# design.net
KiCad netlist of a schematic drawn in Altium Designer
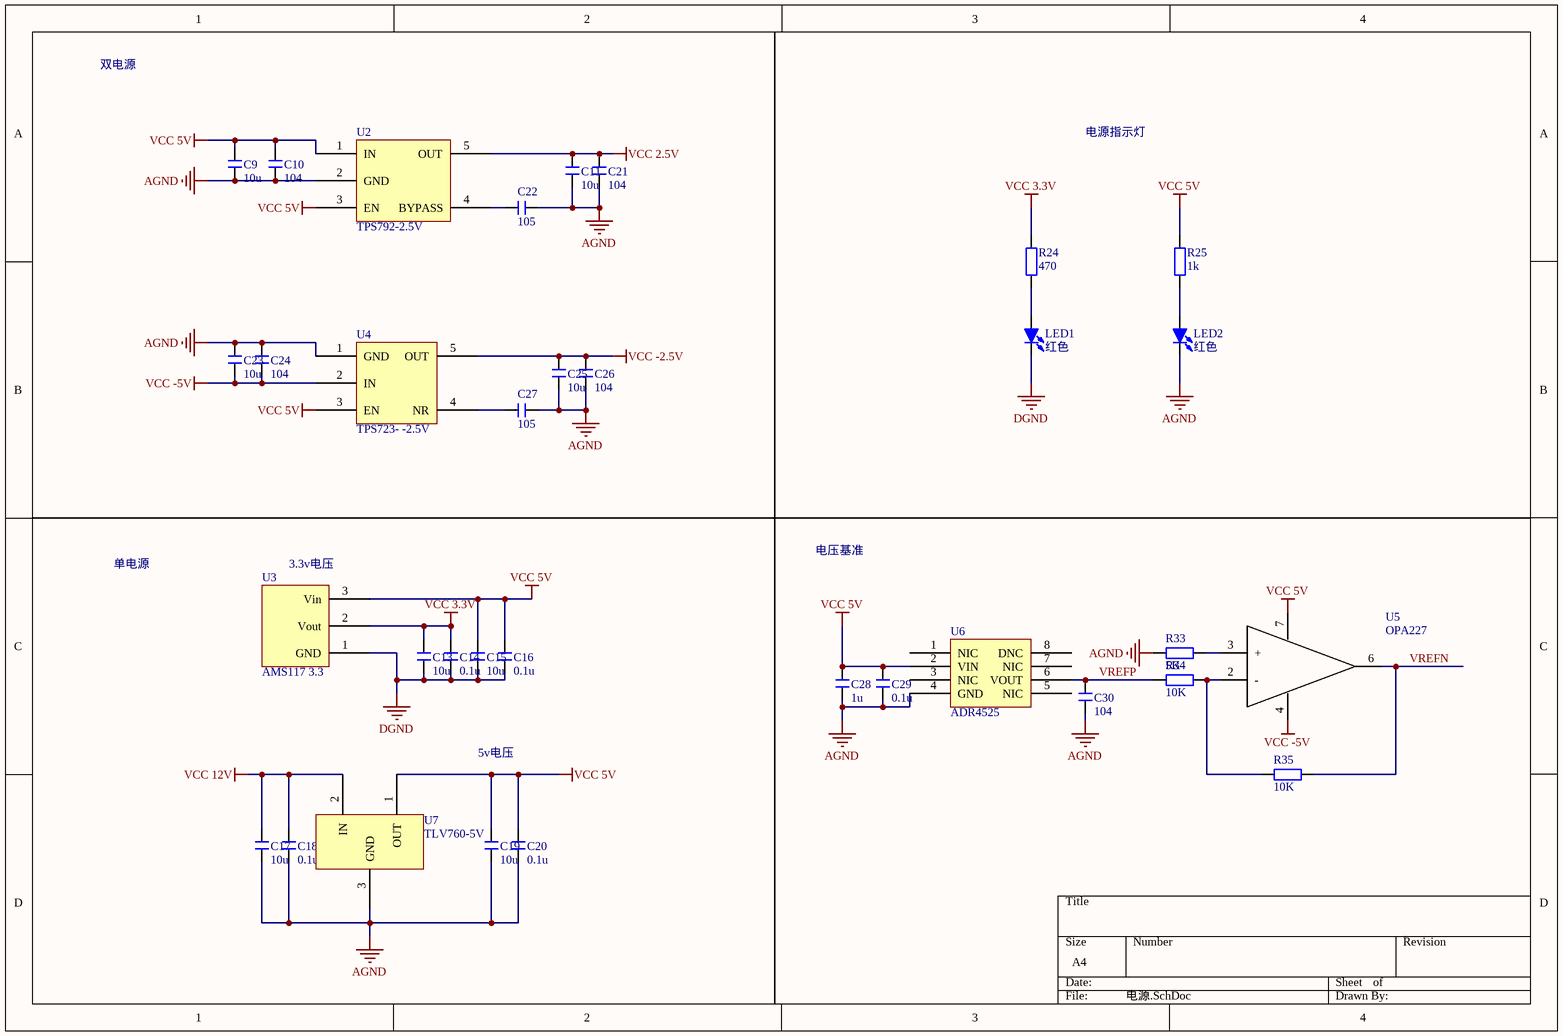
[diagram p0: 电源.SchDoc]

(export (version "E")
  (design (tool "Eeschema 10.0.6"))
  (components
    (comp (ref "C9")
      (value "10u")
      (footprint "C 0805_L")
      (description "无极性贴片电容")
      (fields (field (name "版权归属") "源创客"))
      (libsource (lib "3.1   - 电阻-电容-电感") (part "C"))
    )
    (comp (ref "C10")
      (value "104")
      (footprint "C 0805_L")
      (description "无极性贴片电容")
      (fields (field (name "版权归属") "源创客"))
      (libsource (lib "3.1   - 电阻-电容-电感") (part "C"))
    )
    (comp (ref "C11")
      (value "10u")
      (footprint "C 0805_L")
      (description "无极性贴片电容")
      (fields (field (name "版权归属") "源创客"))
      (libsource (lib "3.1   - 电阻-电容-电感") (part "C"))
    )
    (comp (ref "C13")
      (value "10u")
      (footprint "C 0805_L")
      (description "无极性贴片电容")
      (fields (field (name "版权归属") "源创客"))
      (libsource (lib "3.1   - 电阻-电容-电感") (part "C"))
    )
    (comp (ref "C14")
      (value "0.1u")
      (footprint "C 0805_L")
      (description "无极性贴片电容")
      (fields (field (name "版权归属") "源创客"))
      (libsource (lib "3.1   - 电阻-电容-电感") (part "C"))
    )
    (comp (ref "C15")
      (value "10u")
      (footprint "C 0805_L")
      (description "无极性贴片电容")
      (fields (field (name "版权归属") "源创客"))
      (libsource (lib "3.1   - 电阻-电容-电感") (part "C"))
    )
    (comp (ref "C16")
      (value "0.1u")
      (footprint "C 0805_L")
      (description "无极性贴片电容")
      (fields (field (name "版权归属") "源创客"))
      (libsource (lib "3.1   - 电阻-电容-电感") (part "C"))
    )
    (comp (ref "C17")
      (value "10u")
      (footprint "C 0805_L")
      (description "无极性贴片电容")
      (fields (field (name "版权归属") "源创客"))
      (libsource (lib "3.1   - 电阻-电容-电感") (part "C"))
    )
    (comp (ref "C18")
      (value "0.1u")
      (footprint "C 0805_L")
      (description "无极性贴片电容")
      (fields (field (name "版权归属") "源创客"))
      (libsource (lib "3.1   - 电阻-电容-电感") (part "C"))
    )
    (comp (ref "C19")
      (value "10u")
      (footprint "C 0805_L")
      (description "无极性贴片电容")
      (fields (field (name "版权归属") "源创客"))
      (libsource (lib "3.1   - 电阻-电容-电感") (part "C"))
    )
    (comp (ref "C20")
      (value "0.1u")
      (footprint "C 0805_L")
      (description "无极性贴片电容")
      (fields (field (name "版权归属") "源创客"))
      (libsource (lib "3.1   - 电阻-电容-电感") (part "C"))
    )
    (comp (ref "C21")
      (value "104")
      (footprint "C 0805_L")
      (description "无极性贴片电容")
      (fields (field (name "版权归属") "源创客"))
      (libsource (lib "3.1   - 电阻-电容-电感") (part "C"))
    )
    (comp (ref "C22")
      (value "105")
      (footprint "C 0805_L")
      (description "无极性贴片电容")
      (fields (field (name "版权归属") "源创客"))
      (libsource (lib "3.1   - 电阻-电容-电感") (part "C"))
    )
    (comp (ref "C23")
      (value "10u")
      (footprint "C 0805_L")
      (description "无极性贴片电容")
      (fields (field (name "版权归属") "源创客"))
      (libsource (lib "3.1   - 电阻-电容-电感") (part "C"))
    )
    (comp (ref "C24")
      (value "104")
      (footprint "C 0805_L")
      (description "无极性贴片电容")
      (fields (field (name "版权归属") "源创客"))
      (libsource (lib "3.1   - 电阻-电容-电感") (part "C"))
    )
    (comp (ref "C25")
      (value "10u")
      (footprint "C 0805_L")
      (description "无极性贴片电容")
      (fields (field (name "版权归属") "源创客"))
      (libsource (lib "3.1   - 电阻-电容-电感") (part "C"))
    )
    (comp (ref "C26")
      (value "104")
      (footprint "C 0805_L")
      (description "无极性贴片电容")
      (fields (field (name "版权归属") "源创客"))
      (libsource (lib "3.1   - 电阻-电容-电感") (part "C"))
    )
    (comp (ref "C27")
      (value "105")
      (footprint "C 0805_L")
      (description "无极性贴片电容")
      (fields (field (name "版权归属") "源创客"))
      (libsource (lib "3.1   - 电阻-电容-电感") (part "C"))
    )
    (comp (ref "C28")
      (value "1u")
      (footprint "C 0805_L")
      (description "无极性贴片电容")
      (fields (field (name "版权归属") "源创客"))
      (libsource (lib "3.1   - 电阻-电容-电感") (part "C"))
    )
    (comp (ref "C29")
      (value "0.1u")
      (footprint "C 0805_L")
      (description "无极性贴片电容")
      (fields (field (name "版权归属") "源创客"))
      (libsource (lib "3.1   - 电阻-电容-电感") (part "C"))
    )
    (comp (ref "C30")
      (value "104")
      (footprint "C 0805_L")
      (description "无极性贴片电容")
      (fields (field (name "版权归属") "源创客"))
      (libsource (lib "3.1   - 电阻-电容-电感") (part "C"))
    )
    (comp (ref "LED1")
      (value "红色")
      (footprint "LED 0805G")
      (description "贴片LED")
      (fields (field (name "版权归属") "源创客"))
      (libsource (lib "9.1   - LED") (part "LED-SMD"))
    )
    (comp (ref "LED2")
      (value "红色")
      (footprint "LED 0805G")
      (description "贴片LED")
      (fields (field (name "版权归属") "源创客"))
      (libsource (lib "9.1   - LED") (part "LED-SMD"))
    )
    (comp (ref "R24")
      (value "470")
      (footprint "R 0805_L")
      (description "贴片电阻")
      (fields (field (name "版权归属") "源创客"))
      (libsource (lib "3.1   - 电阻-电容-电感") (part "R"))
    )
    (comp (ref "R25")
      (value "1k")
      (footprint "R 0805_L")
      (description "贴片电阻")
      (fields (field (name "版权归属") "源创客"))
      (libsource (lib "3.1   - 电阻-电容-电感") (part "R"))
    )
    (comp (ref "R33")
      (value "5K")
      (footprint "R 0805_L")
      (description "贴片电阻")
      (fields (field (name "版权归属") "源创客"))
      (libsource (lib "3.1   - 电阻-电容-电感") (part "R"))
    )
    (comp (ref "R34")
      (value "10K")
      (footprint "R 0805_L")
      (description "贴片电阻")
      (fields (field (name "版权归属") "源创客"))
      (libsource (lib "3.1   - 电阻-电容-电感") (part "R"))
    )
    (comp (ref "R35")
      (value "10K")
      (footprint "R 0805_L")
      (description "贴片电阻")
      (fields (field (name "版权归属") "源创客"))
      (libsource (lib "3.1   - 电阻-电容-电感") (part "R"))
    )
    (comp (ref "U2")
      (value "TPS792-2.5V")
      (footprint "SOT23-5N")
      (libsource (lib "TPS792") (part "TPS792-2.5V"))
    )
    (comp (ref "U3") (value "AMS117 3.3") (footprint "SOT223_N") (libsource (lib "AMS1117") (part "AMS117")))
    (comp (ref "U4")
      (value "TPS723- -2.5V")
      (footprint "SOT23-5N")
      (libsource (lib "TPS723") (part "TPS723-  -2.5V"))
    )
    (comp (ref "U5") (value "OPA227") (footprint "SOP8_N") (libsource (lib "运放") (part "OP27")))
    (comp (ref "U6") (value "ADR4525") (footprint "SOP8_N") (libsource (lib "ADR4525") (part "ADR45")))
    (comp (ref "U7") (value "TLV760-5V") (footprint "SOT23-3N") (libsource (lib "TLV760") (part "TLV760")))
  )
  (nets
    (net (code "1") (name "/VREFN") (class "Default")
      (node (ref "R35") (pin "2") (pinfunction "2_2") (pintype "passive"))
      (node (ref "U5") (pin "6") (pinfunction "UOT_6") (pintype "passive"))
    )
    (net (code "2") (name "/VREFP") (class "Default")
      (node (ref "C30") (pin "2") (pinfunction "2_2") (pintype "passive"))
      (node (ref "R34") (pin "1") (pinfunction "1_1") (pintype "passive"))
      (node (ref "U6") (pin "6") (pinfunction "VOUT_6") (pintype "passive"))
    )
    (net (code "3") (name "AGND") (class "Default")
      (node (ref "C10") (pin "1") (pinfunction "1_1") (pintype "passive"))
      (node (ref "C11") (pin "1") (pinfunction "1_1") (pintype "passive"))
      (node (ref "C17") (pin "1") (pinfunction "1_1") (pintype "passive"))
      (node (ref "C18") (pin "1") (pinfunction "1_1") (pintype "passive"))
      (node (ref "C19") (pin "1") (pinfunction "1_1") (pintype "passive"))
      (node (ref "C20") (pin "1") (pinfunction "1_1") (pintype "passive"))
      (node (ref "C21") (pin "1") (pinfunction "1_1") (pintype "passive"))
      (node (ref "C22") (pin "2") (pinfunction "2_2") (pintype "passive"))
      (node (ref "C23") (pin "2") (pinfunction "2_2") (pintype "passive"))
      (node (ref "C24") (pin "2") (pinfunction "2_2") (pintype "passive"))
      (node (ref "C25") (pin "1") (pinfunction "1_1") (pintype "passive"))
      (node (ref "C26") (pin "1") (pinfunction "1_1") (pintype "passive"))
      (node (ref "C27") (pin "2") (pinfunction "2_2") (pintype "passive"))
      (node (ref "C28") (pin "1") (pinfunction "1_1") (pintype "passive"))
      (node (ref "C29") (pin "1") (pinfunction "1_1") (pintype "passive"))
      (node (ref "C30") (pin "1") (pinfunction "1_1") (pintype "passive"))
      (node (ref "C9") (pin "1") (pinfunction "1_1") (pintype "passive"))
      (node (ref "LED2") (pin "2") (pinfunction "K_2") (pintype "passive"))
      (node (ref "R33") (pin "2") (pinfunction "2_2") (pintype "passive"))
      (node (ref "U2") (pin "2") (pinfunction "GND_2") (pintype "passive"))
      (node (ref "U4") (pin "1") (pinfunction "GND_1") (pintype "passive"))
      (node (ref "U6") (pin "4") (pinfunction "GND_4") (pintype "passive"))
      (node (ref "U7") (pin "3") (pinfunction "GND_3") (pintype "passive"))
    )
    (net (code "4") (name "DGND") (class "Default")
      (node (ref "C13") (pin "1") (pinfunction "1_1") (pintype "passive"))
      (node (ref "C14") (pin "1") (pinfunction "1_1") (pintype "passive"))
      (node (ref "C15") (pin "1") (pinfunction "1_1") (pintype "passive"))
      (node (ref "C16") (pin "1") (pinfunction "1_1") (pintype "passive"))
      (node (ref "LED1") (pin "2") (pinfunction "K_2") (pintype "passive"))
      (node (ref "U3") (pin "1") (pinfunction "GND_1") (pintype "passive"))
    )
    (net (code "5") (name "Net-(LED1-A)") (class "Default")
      (node (ref "LED1") (pin "1") (pinfunction "A_1") (pintype "passive"))
      (node (ref "R24") (pin "1") (pinfunction "1_1") (pintype "passive"))
    )
    (net (code "6") (name "Net-(LED2-A)") (class "Default")
      (node (ref "LED2") (pin "1") (pinfunction "A_1") (pintype "passive"))
      (node (ref "R25") (pin "1") (pinfunction "1_1") (pintype "passive"))
    )
    (net (code "7") (name "Net-(U2-BYPASS)") (class "Default")
      (node (ref "C22") (pin "1") (pinfunction "1_1") (pintype "passive"))
      (node (ref "U2") (pin "4") (pinfunction "BYPASS_4") (pintype "passive"))
    )
    (net (code "8") (name "Net-(U4-NR)") (class "Default")
      (node (ref "C27") (pin "1") (pinfunction "1_1") (pintype "passive"))
      (node (ref "U4") (pin "4") (pinfunction "NR_4") (pintype "passive"))
    )
    (net (code "9") (name "Net-(U5-+)") (class "Default")
      (node (ref "R33") (pin "1") (pinfunction "1_1") (pintype "passive"))
      (node (ref "U5") (pin "3") (pinfunction "+_3") (pintype "passive"))
    )
    (net (code "10") (name "Net-(U5--)") (class "Default")
      (node (ref "R34") (pin "2") (pinfunction "2_2") (pintype "passive"))
      (node (ref "R35") (pin "1") (pinfunction "1_1") (pintype "passive"))
      (node (ref "U5") (pin "2") (pinfunction "-_2") (pintype "passive"))
    )
    (net (code "11") (name "VCC -2.5V") (class "Default")
      (node (ref "C25") (pin "2") (pinfunction "2_2") (pintype "passive"))
      (node (ref "C26") (pin "2") (pinfunction "2_2") (pintype "passive"))
      (node (ref "U4") (pin "5") (pinfunction "OUT_5") (pintype "passive"))
    )
    (net (code "12") (name "VCC -5V") (class "Default")
      (node (ref "C23") (pin "1") (pinfunction "1_1") (pintype "passive"))
      (node (ref "C24") (pin "1") (pinfunction "1_1") (pintype "passive"))
      (node (ref "U4") (pin "2") (pinfunction "IN_2") (pintype "passive"))
      (node (ref "U5") (pin "4") (pinfunction "VSS_4") (pintype "passive"))
    )
    (net (code "13") (name "VCC 2.5V") (class "Default")
      (node (ref "C11") (pin "2") (pinfunction "2_2") (pintype "passive"))
      (node (ref "C21") (pin "2") (pinfunction "2_2") (pintype "passive"))
      (node (ref "U2") (pin "5") (pinfunction "OUT_5") (pintype "passive"))
    )
    (net (code "14") (name "VCC 3.3V") (class "Default")
      (node (ref "C13") (pin "2") (pinfunction "2_2") (pintype "passive"))
      (node (ref "C14") (pin "2") (pinfunction "2_2") (pintype "passive"))
      (node (ref "R24") (pin "2") (pinfunction "2_2") (pintype "passive"))
      (node (ref "U3") (pin "2") (pinfunction "Vout_2") (pintype "passive"))
    )
    (net (code "15") (name "VCC 5V") (class "Default")
      (node (ref "C10") (pin "2") (pinfunction "2_2") (pintype "passive"))
      (node (ref "C15") (pin "2") (pinfunction "2_2") (pintype "passive"))
      (node (ref "C16") (pin "2") (pinfunction "2_2") (pintype "passive"))
      (node (ref "C19") (pin "2") (pinfunction "2_2") (pintype "passive"))
      (node (ref "C20") (pin "2") (pinfunction "2_2") (pintype "passive"))
      (node (ref "C28") (pin "2") (pinfunction "2_2") (pintype "passive"))
      (node (ref "C29") (pin "2") (pinfunction "2_2") (pintype "passive"))
      (node (ref "C9") (pin "2") (pinfunction "2_2") (pintype "passive"))
      (node (ref "R25") (pin "2") (pinfunction "2_2") (pintype "passive"))
      (node (ref "U2") (pin "1") (pinfunction "IN_1") (pintype "passive"))
      (node (ref "U2") (pin "3") (pinfunction "EN_3") (pintype "passive"))
      (node (ref "U3") (pin "3") (pinfunction "Vin_3") (pintype "passive"))
      (node (ref "U4") (pin "3") (pinfunction "EN_3") (pintype "passive"))
      (node (ref "U5") (pin "7") (pinfunction "VCC_7") (pintype "passive"))
      (node (ref "U6") (pin "2") (pinfunction "VIN_2") (pintype "passive"))
      (node (ref "U7") (pin "1") (pinfunction "OUT_1") (pintype "passive"))
    )
    (net (code "16") (name "VCC 12V") (class "Default")
      (node (ref "C17") (pin "2") (pinfunction "2_2") (pintype "passive"))
      (node (ref "C18") (pin "2") (pinfunction "2_2") (pintype "passive"))
      (node (ref "U7") (pin "2") (pinfunction "IN_2") (pintype "passive"))
    )
    (net (code "17") (name "unconnected-(U6-DNC-Pad8)") (class "Default")
      (node (ref "U6") (pin "8") (pinfunction "DNC_8") (pintype "passive"))
    )
    (net (code "18") (name "unconnected-(U6-NIC-Pad1)") (class "Default")
      (node (ref "U6") (pin "1") (pinfunction "NIC_1") (pintype "passive"))
    )
    (net (code "19") (name "unconnected-(U6-NIC-Pad3)") (class "Default")
      (node (ref "U6") (pin "3") (pinfunction "NIC_3") (pintype "passive"))
    )
    (net (code "20") (name "unconnected-(U6-NIC-Pad5)") (class "Default")
      (node (ref "U6") (pin "5") (pinfunction "NIC_5") (pintype "passive"))
    )
    (net (code "21") (name "unconnected-(U6-NIC-Pad7)") (class "Default")
      (node (ref "U6") (pin "7") (pinfunction "NIC_7") (pintype "passive"))
    )
  )
)
